# 1-Schematic.net
KiCad netlist of a schematic drawn in EasyEDA
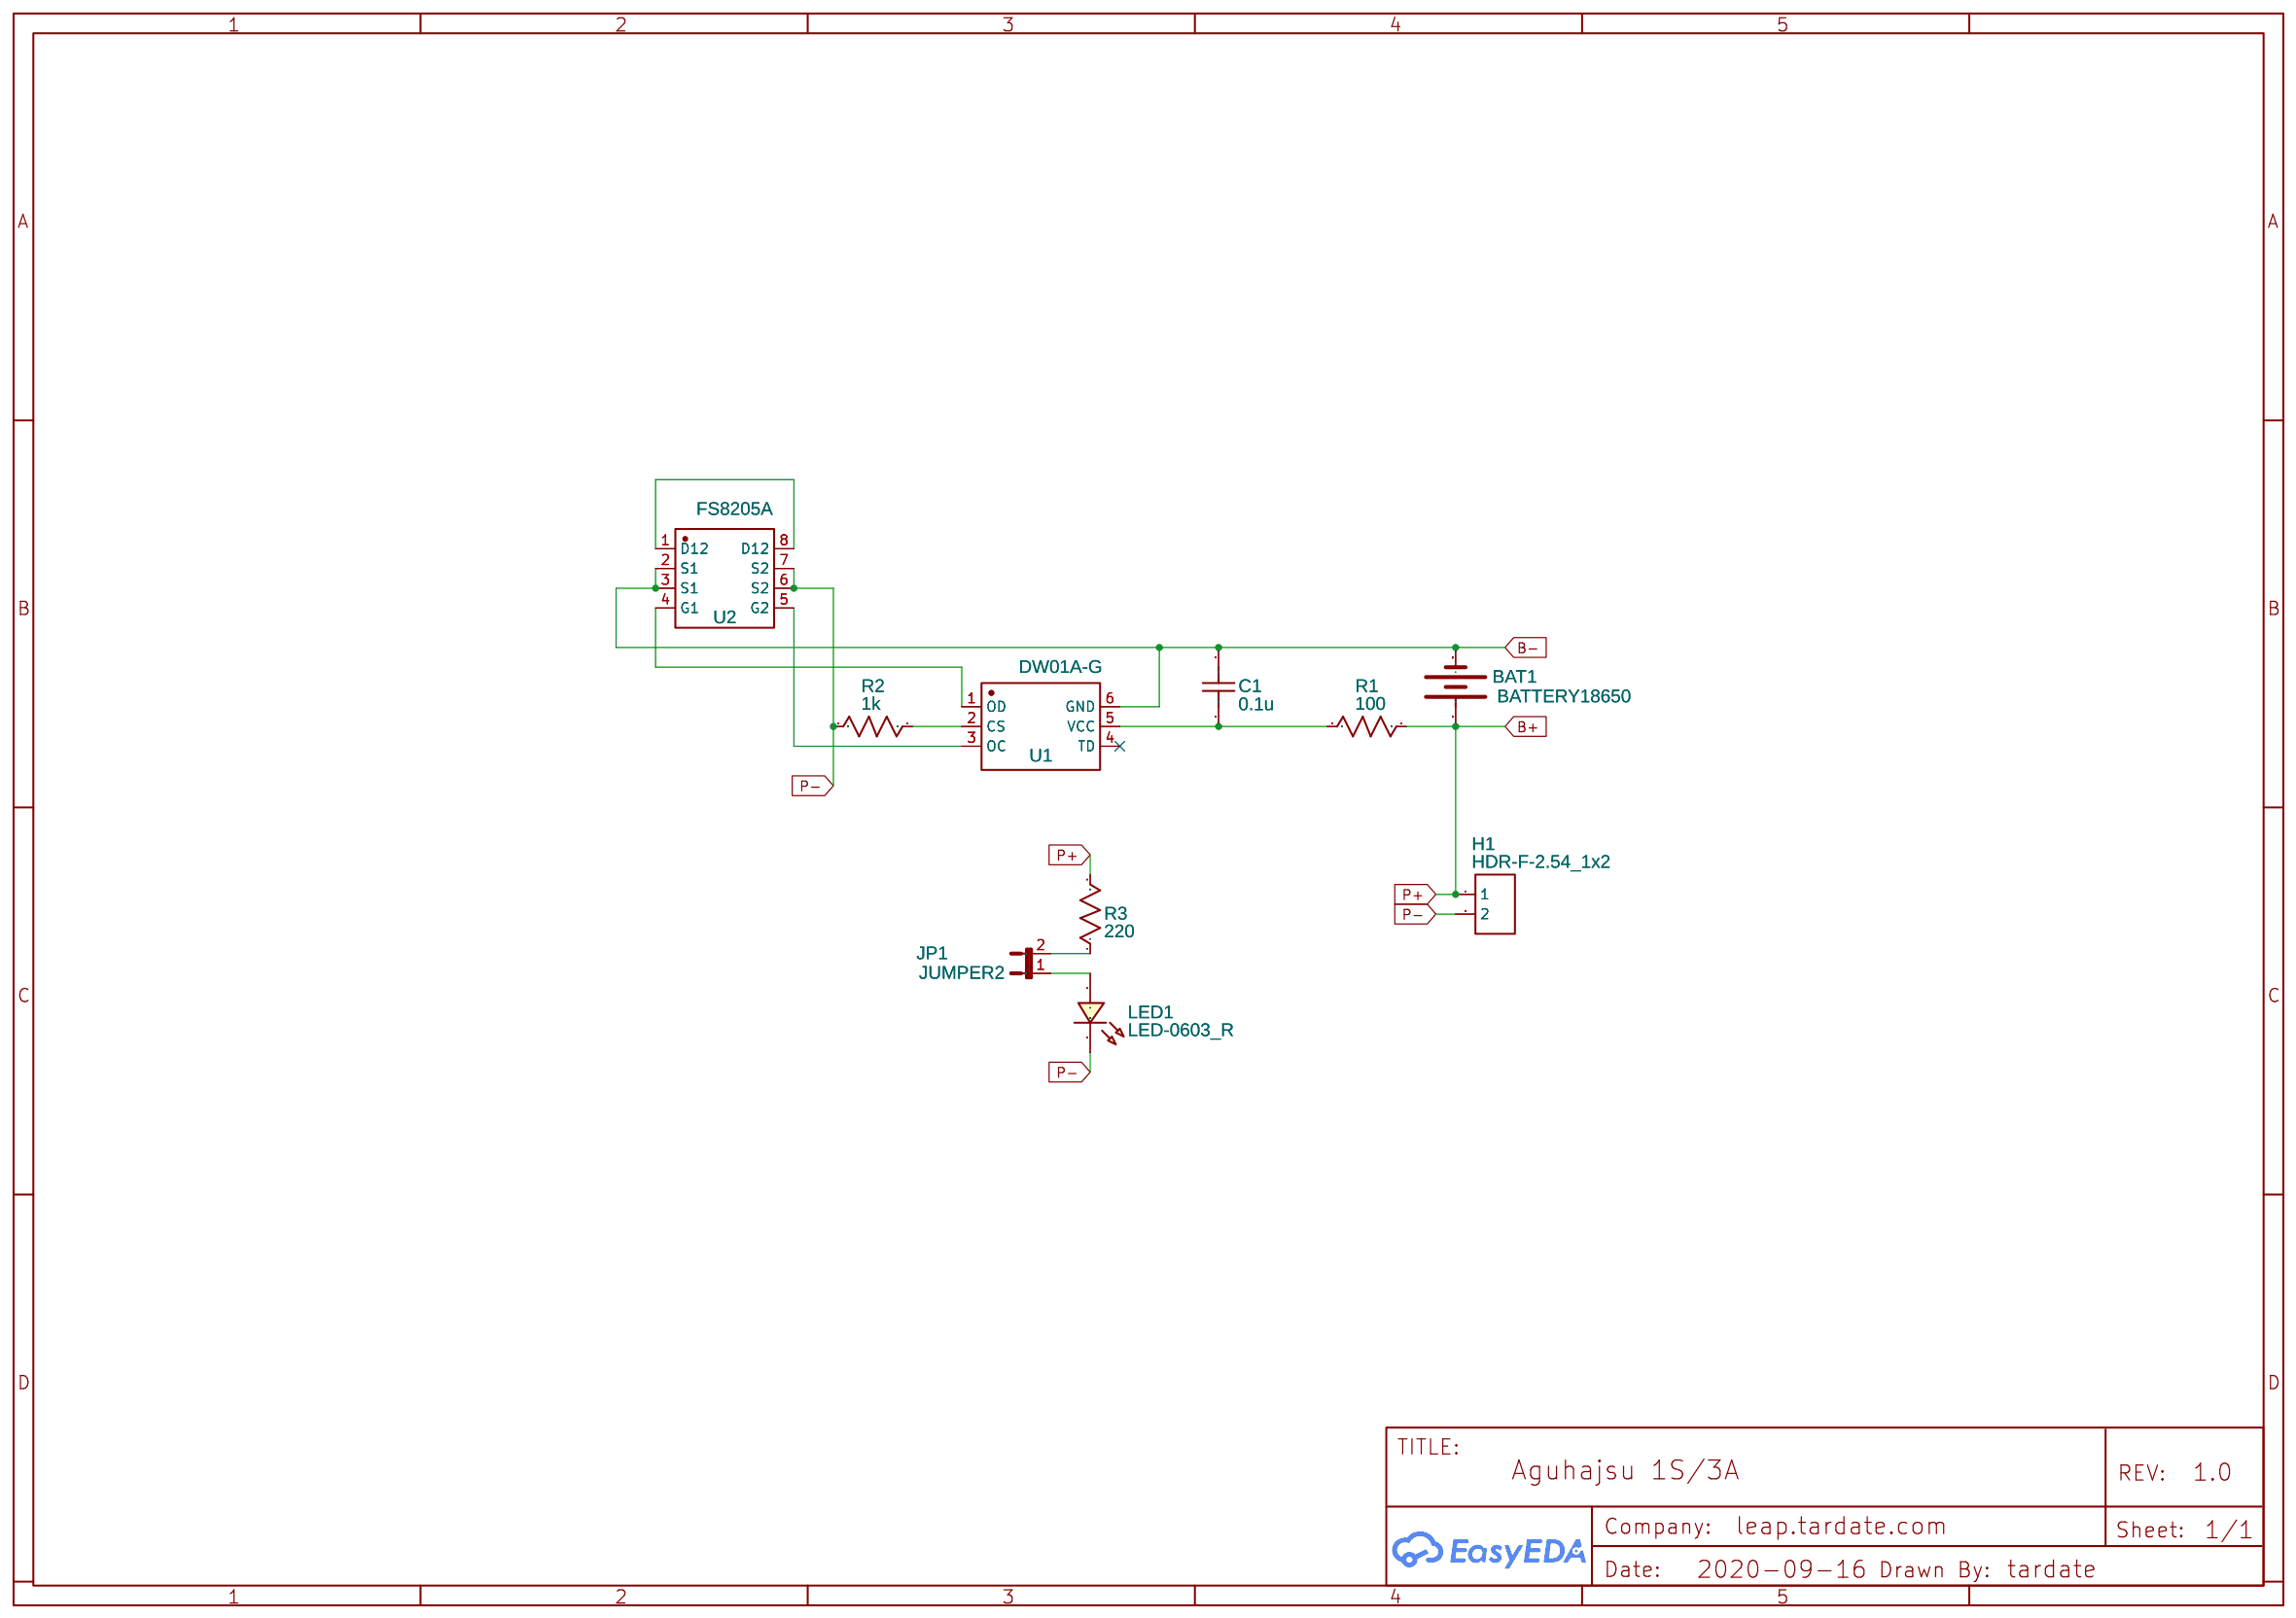
[diagram p0: schematic sheet]

(export (version "E")
  (design (tool "Eeschema 10.0.6"))
  (components
    (comp (ref "BAT1") (value "BATTERY18650") (libsource (lib "") (part "BATTERY18650")))
    (comp (ref "C1") (value "0.1u") (libsource (lib "") (part "C_0603_US")))
    (comp (ref "H1")
      (value "HDR-F-2.54_1x2")
      (fields (field (name "BOM_Supplier Part") "C49661"))
      (libsource (lib "") (part "HDR-F-2.54_1x2"))
    )
    (comp (ref "JP1") (value "JUMPER2") (libsource (lib "") (part "JUMPER2")))
    (comp (ref "LED1")
      (value "LED-0603_R")
      (fields
        (field (name "BOM_Manufacturer Part") "19-217/R6C-AL1M2VY/3T")
        (field (name "BOM_Supplier Part") "C72044")
      )
      (libsource (lib "") (part "LED-0603_R"))
    )
    (comp (ref "R1") (value "100") (libsource (lib "") (part "R_0603_US")))
    (comp (ref "R2") (value "1k") (libsource (lib "") (part "R_0603_US")))
    (comp (ref "R3") (value "220") (libsource (lib "") (part "R_0603_US_1")))
    (comp (ref "U1")
      (value "DW01A-G")
      (fields (field (name "BOM_Supplier Part") "C61503"))
      (libsource (lib "") (part "DW01A-G"))
    )
    (comp (ref "U2")
      (value "FS8205A")
      (fields (field (name "BOM_Supplier Part") "C16052"))
      (libsource (lib "") (part "FS8205A"))
    )
  )
  (nets
    (net (code "1") (name "B+") (class "Default")
      (node (ref "BAT1") (pin "PWR@1") (pinfunction "+_PWR@1") (pintype "passive"))
      (node (ref "H1") (pin "1") (pinfunction "1_1") (pintype "input"))
      (node (ref "R1") (pin "1") (pinfunction "1_1") (pintype "unspecified"))
      (node (ref "R3") (pin "2") (pinfunction "2_2") (pintype "unspecified"))
    )
    (net (code "2") (name "B-") (class "Default")
      (node (ref "BAT1") (pin "GND@1") (pinfunction "-_GND@1") (pintype "passive"))
      (node (ref "C1") (pin "1") (pinfunction "1_1") (pintype "unspecified"))
      (node (ref "U1") (pin "6") (pinfunction "GND_6") (pintype "unspecified"))
      (node (ref "U2") (pin "2") (pinfunction "S1_2") (pintype "unspecified"))
      (node (ref "U2") (pin "3") (pinfunction "S1_3") (pintype "unspecified"))
    )
    (net (code "3") (name "Net-(JP1-Pad1)") (class "Default")
      (node (ref "JP1") (pin "1") (pinfunction "1_1") (pintype "unspecified"))
      (node (ref "LED1") (pin "1") (pinfunction "1_1") (pintype "unspecified"))
    )
    (net (code "4") (name "Net-(JP1-Pad2)") (class "Default")
      (node (ref "JP1") (pin "2") (pinfunction "2_2") (pintype "unspecified"))
      (node (ref "R3") (pin "1") (pinfunction "1_1") (pintype "unspecified"))
    )
    (net (code "5") (name "Net-(U1-CS)") (class "Default")
      (node (ref "R2") (pin "1") (pinfunction "1_1") (pintype "unspecified"))
      (node (ref "U1") (pin "2") (pinfunction "CS_2") (pintype "unspecified"))
    )
    (net (code "6") (name "Net-(U1-OC)") (class "Default")
      (node (ref "U1") (pin "3") (pinfunction "OC_3") (pintype "unspecified"))
      (node (ref "U2") (pin "5") (pinfunction "G2_5") (pintype "unspecified"))
    )
    (net (code "7") (name "Net-(U1-OD)") (class "Default")
      (node (ref "U1") (pin "1") (pinfunction "OD_1") (pintype "unspecified"))
      (node (ref "U2") (pin "4") (pinfunction "G1_4") (pintype "unspecified"))
    )
    (net (code "8") (name "Net-(U1-VCC)") (class "Default")
      (node (ref "C1") (pin "2") (pinfunction "2_2") (pintype "unspecified"))
      (node (ref "R1") (pin "2") (pinfunction "2_2") (pintype "unspecified"))
      (node (ref "U1") (pin "5") (pinfunction "VCC_5") (pintype "unspecified"))
    )
    (net (code "9") (name "Net-(U2-D12-Pad1)") (class "Default")
      (node (ref "U2") (pin "1") (pinfunction "D12_1") (pintype "unspecified"))
      (node (ref "U2") (pin "8") (pinfunction "D12_8") (pintype "unspecified"))
    )
    (net (code "10") (name "P-") (class "Default")
      (node (ref "H1") (pin "2") (pinfunction "2_2") (pintype "input"))
      (node (ref "LED1") (pin "2") (pinfunction "2_2") (pintype "unspecified"))
      (node (ref "R2") (pin "2") (pinfunction "2_2") (pintype "unspecified"))
      (node (ref "U2") (pin "6") (pinfunction "S2_6") (pintype "unspecified"))
      (node (ref "U2") (pin "7") (pinfunction "S2_7") (pintype "unspecified"))
    )
    (net (code "11") (name "unconnected-(U1-TD-Pad4)") (class "Default")
      (node (ref "U1") (pin "4") (pinfunction "TD_4") (pintype "unspecified+no_connect"))
    )
  )
)
